# powercon_board.net
KiCad netlist of a schematic drawn in EAGLE
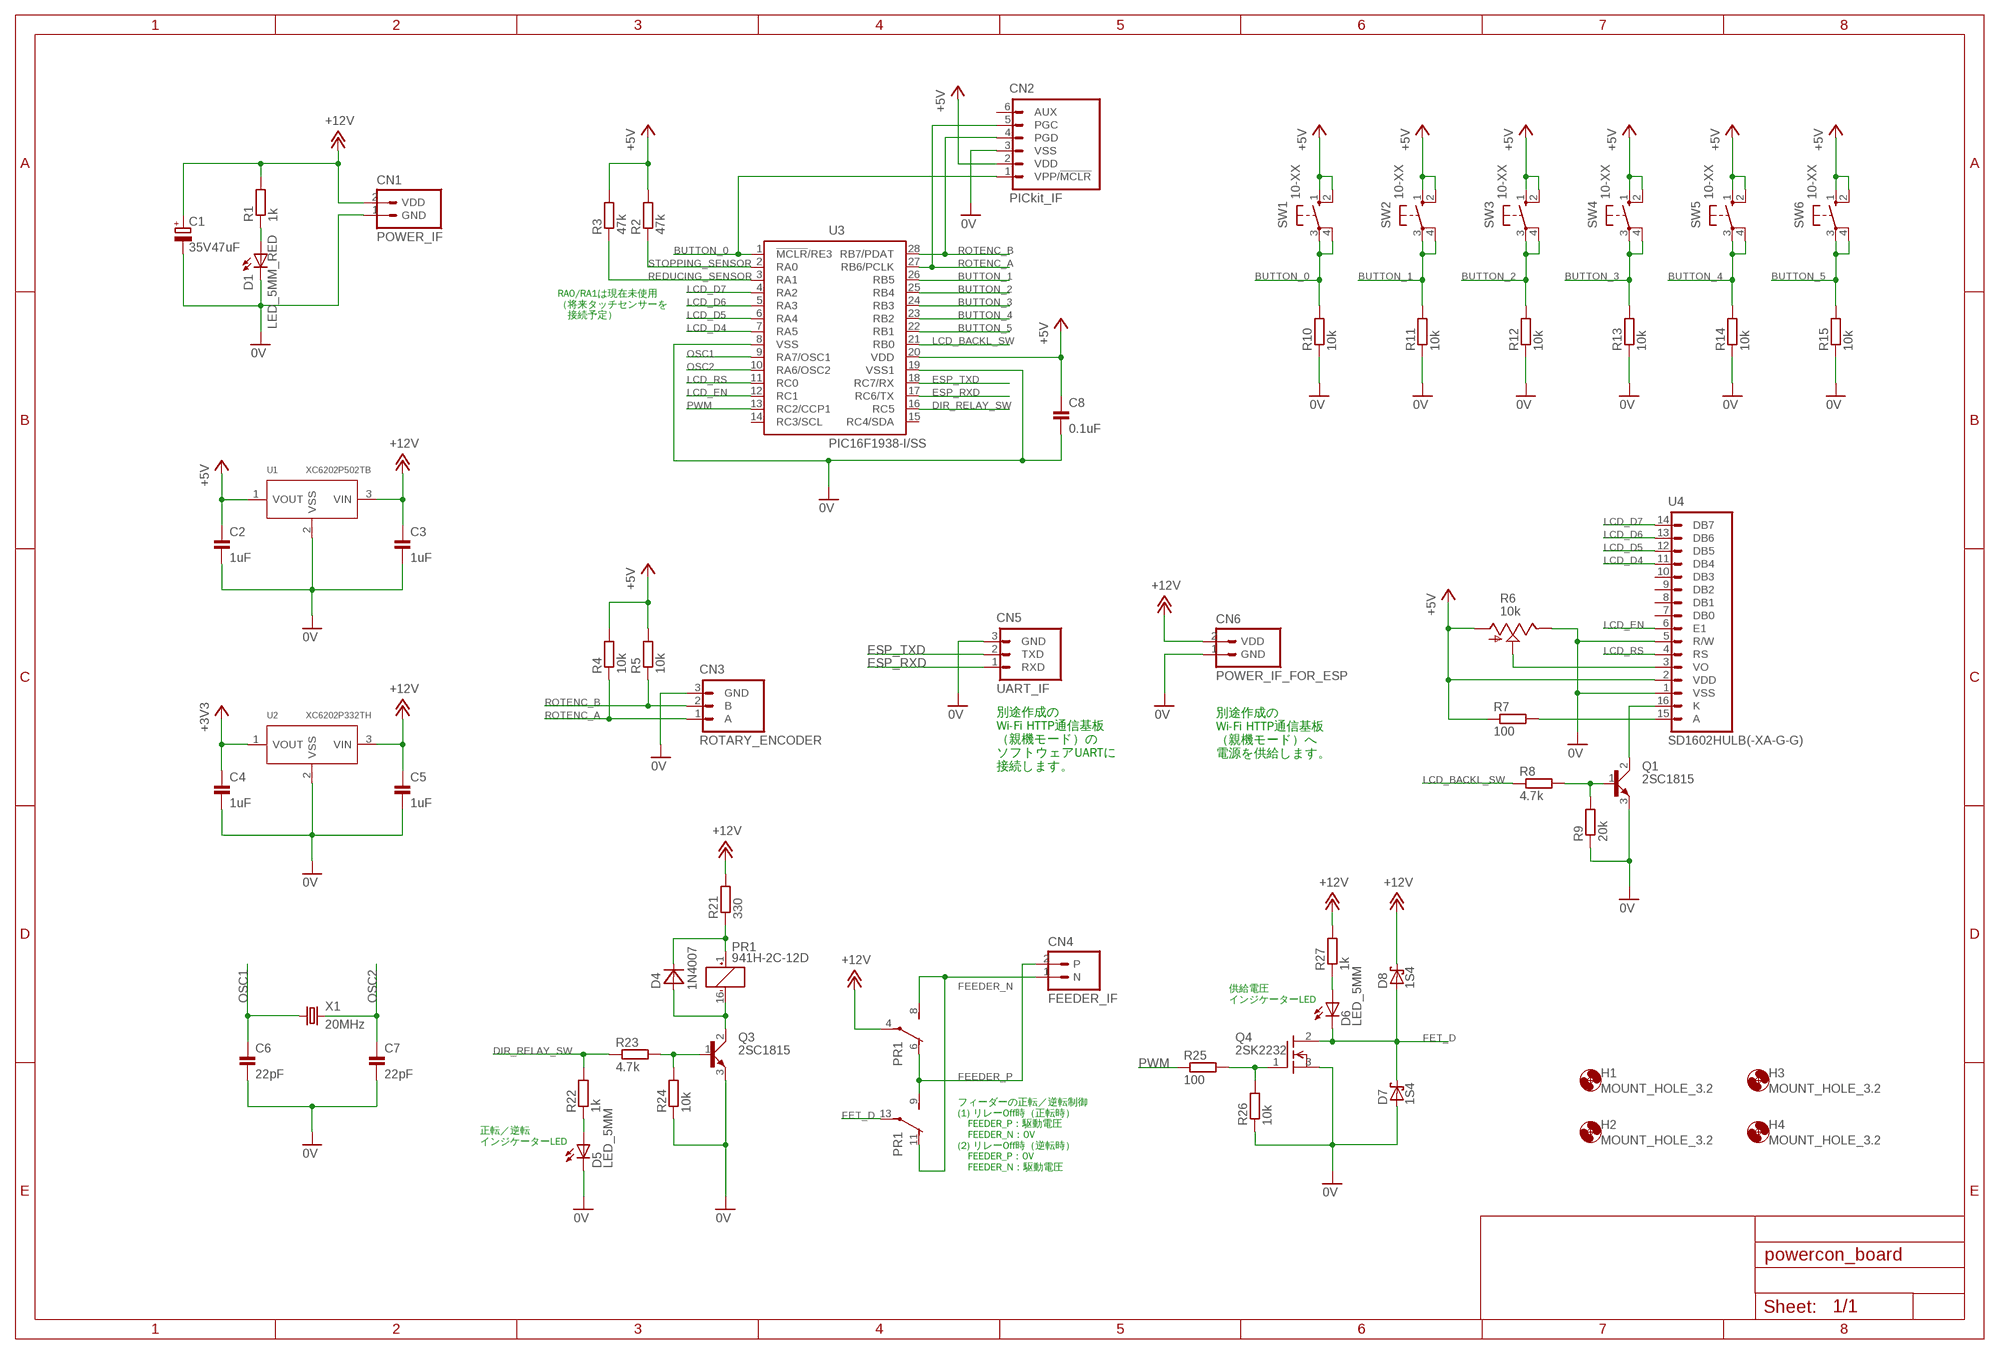
[diagram p0: schematic, sheet 1]

(export (version "E")
  (design (tool "Eeschema 10.0.6"))
  (components
    (comp (ref "C1")
      (value "35V47uF")
      (footprint "eagle-import:ELECAP_200MIL")
      (libsource (lib "eagle-import") (part "ELECAP_200MIL"))
    )
    (comp (ref "C2")
      (value "1uF")
      (footprint "eagle-import:CAP_200MIL")
      (libsource (lib "eagle-import") (part "CAP_200MIL"))
    )
    (comp (ref "C3")
      (value "1uF")
      (footprint "eagle-import:CAP_200MIL")
      (libsource (lib "eagle-import") (part "CAP_200MIL"))
    )
    (comp (ref "C4")
      (value "1uF")
      (footprint "eagle-import:CAP_200MIL")
      (libsource (lib "eagle-import") (part "CAP_200MIL"))
    )
    (comp (ref "C5")
      (value "1uF")
      (footprint "eagle-import:CAP_200MIL")
      (libsource (lib "eagle-import") (part "CAP_200MIL"))
    )
    (comp (ref "C6")
      (value "22pF")
      (footprint "eagle-import:CAP_200MIL")
      (libsource (lib "eagle-import") (part "CAP_200MIL"))
    )
    (comp (ref "C7")
      (value "22pF")
      (footprint "eagle-import:CAP_200MIL")
      (libsource (lib "eagle-import") (part "CAP_200MIL"))
    )
    (comp (ref "C8")
      (value "0.1uF")
      (footprint "eagle-import:CAP_200MIL")
      (libsource (lib "eagle-import") (part "CAP_200MIL"))
    )
    (comp (ref "CN1")
      (value "POWER_IF")
      (footprint "eagle-import:HEADER_2PIN_POWER_IF")
      (libsource (lib "eagle-import") (part "POWER_IF"))
    )
    (comp (ref "CN2")
      (value "PICkit_IF")
      (footprint "eagle-import:HEADER_6PIN")
      (libsource (lib "eagle-import") (part "PIC_CN_H"))
    )
    (comp (ref "CN3")
      (value "ROTARY_ENCODER")
      (footprint "eagle-import:HEADER_3PIN_ROT_ENC")
      (libsource (lib "eagle-import") (part "ROTARY_ENCODER"))
    )
    (comp (ref "CN4")
      (value "FEEDER_IF")
      (footprint "eagle-import:HEADER_2PIN_FEEDER_IF")
      (libsource (lib "eagle-import") (part "FEEDER_IF"))
    )
    (comp (ref "CN5")
      (value "UART_IF")
      (footprint "eagle-import:HEADER_3PIN_UART_IF")
      (libsource (lib "eagle-import") (part "UART_IF"))
    )
    (comp (ref "CN6")
      (value "POWER_IF_FOR_ESP")
      (footprint "eagle-import:HEADER_2PIN_POWER_IF")
      (libsource (lib "eagle-import") (part "POWER_IF"))
    )
    (comp (ref "D1")
      (value "LED_5MM_RED")
      (footprint "eagle-import:LED5MM")
      (libsource (lib "eagle-import") (part "LED_5MM"))
    )
    (comp (ref "D4")
      (value "1N4007")
      (footprint "eagle-import:DIODE_300MIL")
      (libsource (lib "eagle-import") (part "1N4007"))
    )
    (comp (ref "D5")
      (value "LED_5MM")
      (footprint "eagle-import:LED5MM")
      (libsource (lib "eagle-import") (part "LED_5MM"))
    )
    (comp (ref "D6")
      (value "LED_5MM")
      (footprint "eagle-import:LED5MM")
      (libsource (lib "eagle-import") (part "LED_5MM"))
    )
    (comp (ref "D7")
      (value "1S4")
      (footprint "eagle-import:DIODE-200MIL")
      (libsource (lib "eagle-import") (part "1S4"))
    )
    (comp (ref "D8")
      (value "1S4")
      (footprint "eagle-import:DIODE-200MIL")
      (libsource (lib "eagle-import") (part "1S4"))
    )
    (comp (ref "H1")
      (value "MOUNT_HOLE_3.2")
      (footprint "eagle-import:3,2")
      (libsource (lib "eagle-import") (part "MOUNT_HOLE_3.2"))
    )
    (comp (ref "H2")
      (value "MOUNT_HOLE_3.2")
      (footprint "eagle-import:3,2")
      (libsource (lib "eagle-import") (part "MOUNT_HOLE_3.2"))
    )
    (comp (ref "H3")
      (value "MOUNT_HOLE_3.2")
      (footprint "eagle-import:3,2")
      (libsource (lib "eagle-import") (part "MOUNT_HOLE_3.2"))
    )
    (comp (ref "H4")
      (value "MOUNT_HOLE_3.2")
      (footprint "eagle-import:3,2")
      (libsource (lib "eagle-import") (part "MOUNT_HOLE_3.2"))
    )
    (comp (ref "PR1")
      (value "941H-2C-12D")
      (footprint "eagle-import:941H-2C")
      (libsource (lib "eagle-import") (part "941H-2C-12D"))
    )
    (comp (ref "Q1")
      (value "2SC1815")
      (footprint "eagle-import:TO-92NL")
      (libsource (lib "eagle-import") (part "2SC1815"))
    )
    (comp (ref "Q3")
      (value "2SC1815")
      (footprint "eagle-import:TO-92NL")
      (libsource (lib "eagle-import") (part "2SC1815"))
    )
    (comp (ref "Q4")
      (value "2SK2232")
      (footprint "eagle-import:TO-220")
      (libsource (lib "eagle-import") (part "2SK2232"))
    )
    (comp (ref "R1")
      (value "1k")
      (footprint "eagle-import:RESISTOR_0207_300MIL")
      (libsource (lib "eagle-import") (part "RESISTOR_300MIL"))
    )
    (comp (ref "R2")
      (value "47k")
      (footprint "eagle-import:RESISTOR_0207_300MIL")
      (libsource (lib "eagle-import") (part "RESISTOR_300MIL"))
    )
    (comp (ref "R3")
      (value "47k")
      (footprint "eagle-import:RESISTOR_0207_300MIL")
      (libsource (lib "eagle-import") (part "RESISTOR_300MIL"))
    )
    (comp (ref "R4")
      (value "10k")
      (footprint "eagle-import:RESISTOR_0207_300MIL")
      (libsource (lib "eagle-import") (part "RESISTOR_300MIL"))
    )
    (comp (ref "R5")
      (value "10k")
      (footprint "eagle-import:RESISTOR_0207_300MIL")
      (libsource (lib "eagle-import") (part "RESISTOR_300MIL"))
    )
    (comp (ref "R6")
      (value "10k")
      (footprint "eagle-import:GF063XB")
      (libsource (lib "eagle-import") (part "GF063XB"))
    )
    (comp (ref "R7")
      (value "100")
      (footprint "eagle-import:RESISTOR_0207_300MIL")
      (libsource (lib "eagle-import") (part "RESISTOR_300MIL"))
    )
    (comp (ref "R8")
      (value "4.7k")
      (footprint "eagle-import:RESISTOR_0207_300MIL")
      (libsource (lib "eagle-import") (part "RESISTOR_300MIL"))
    )
    (comp (ref "R9")
      (value "20k")
      (footprint "eagle-import:RESISTOR_0207_300MIL")
      (libsource (lib "eagle-import") (part "RESISTOR_300MIL"))
    )
    (comp (ref "R10")
      (value "10k")
      (footprint "eagle-import:RESISTOR_0207_300MIL")
      (libsource (lib "eagle-import") (part "RESISTOR_300MIL"))
    )
    (comp (ref "R11")
      (value "10k")
      (footprint "eagle-import:RESISTOR_0207_300MIL")
      (libsource (lib "eagle-import") (part "RESISTOR_300MIL"))
    )
    (comp (ref "R12")
      (value "10k")
      (footprint "eagle-import:RESISTOR_0207_300MIL")
      (libsource (lib "eagle-import") (part "RESISTOR_300MIL"))
    )
    (comp (ref "R13")
      (value "10k")
      (footprint "eagle-import:RESISTOR_0207_300MIL")
      (libsource (lib "eagle-import") (part "RESISTOR_300MIL"))
    )
    (comp (ref "R14")
      (value "10k")
      (footprint "eagle-import:RESISTOR_0207_300MIL")
      (libsource (lib "eagle-import") (part "RESISTOR_300MIL"))
    )
    (comp (ref "R15")
      (value "10k")
      (footprint "eagle-import:RESISTOR_0207_300MIL")
      (libsource (lib "eagle-import") (part "RESISTOR_300MIL"))
    )
    (comp (ref "R21")
      (value "330")
      (footprint "eagle-import:RESISTOR_0207_300MIL")
      (libsource (lib "eagle-import") (part "RESISTOR_300MIL"))
    )
    (comp (ref "R22")
      (value "1k")
      (footprint "eagle-import:RESISTOR_0207_300MIL")
      (libsource (lib "eagle-import") (part "RESISTOR_300MIL"))
    )
    (comp (ref "R23")
      (value "4.7k")
      (footprint "eagle-import:RESISTOR_0207_300MIL")
      (libsource (lib "eagle-import") (part "RESISTOR_300MIL"))
    )
    (comp (ref "R24")
      (value "10k")
      (footprint "eagle-import:RESISTOR_0207_300MIL")
      (libsource (lib "eagle-import") (part "RESISTOR_300MIL"))
    )
    (comp (ref "R25")
      (value "100")
      (footprint "eagle-import:RESISTOR_0207_300MIL")
      (libsource (lib "eagle-import") (part "RESISTOR_300MIL"))
    )
    (comp (ref "R26")
      (value "10k")
      (footprint "eagle-import:RESISTOR_0207_300MIL")
      (libsource (lib "eagle-import") (part "RESISTOR_300MIL"))
    )
    (comp (ref "R27")
      (value "1k")
      (footprint "eagle-import:RESISTOR_0207_300MIL")
      (libsource (lib "eagle-import") (part "RESISTOR_300MIL"))
    )
    (comp (ref "SW1")
      (value "10-XX")
      (footprint "eagle-import:B3F-10XX")
      (libsource (lib "eagle-import") (part "10-XX"))
    )
    (comp (ref "SW2")
      (value "10-XX")
      (footprint "eagle-import:B3F-10XX")
      (libsource (lib "eagle-import") (part "10-XX"))
    )
    (comp (ref "SW3")
      (value "10-XX")
      (footprint "eagle-import:B3F-10XX")
      (libsource (lib "eagle-import") (part "10-XX"))
    )
    (comp (ref "SW4")
      (value "10-XX")
      (footprint "eagle-import:B3F-10XX")
      (libsource (lib "eagle-import") (part "10-XX"))
    )
    (comp (ref "SW5")
      (value "10-XX")
      (footprint "eagle-import:B3F-10XX")
      (libsource (lib "eagle-import") (part "10-XX"))
    )
    (comp (ref "SW6")
      (value "10-XX")
      (footprint "eagle-import:B3F-10XX")
      (libsource (lib "eagle-import") (part "10-XX"))
    )
    (comp (ref "U1")
      (value "XC6202P502TB")
      (footprint "eagle-import:TO92-LINE")
      (libsource (lib "eagle-import") (part "XC6202P502TB"))
    )
    (comp (ref "U2")
      (value "XC6202P332TH")
      (footprint "eagle-import:TO92-LINE")
      (libsource (lib "eagle-import") (part "XC6202P332TH"))
    )
    (comp (ref "U3")
      (value "PIC16F1938-I/SS")
      (footprint "eagle-import:SSOP28")
      (libsource (lib "eagle-import") (part "PIC16F1938-I/SS"))
    )
    (comp (ref "U4")
      (value "SD1602HULB(-XA-G-G)")
      (footprint "eagle-import:HEADER_16PIN_SD1602")
      (libsource (lib "eagle-import") (part "SD1602HULB(-XA-G-G)"))
    )
    (comp (ref "X1")
      (value "20MHz")
      (footprint "eagle-import:HC-49_S")
      (libsource (lib "eagle-import") (part "HUSG-20.000-20"))
    )
  )
  (nets
    (net (code "1") (name "+3V3") (class "Default")
      (node (ref "C4") (pin "1") (pinfunction "1_1") (pintype "passive"))
      (node (ref "U2") (pin "1") (pinfunction "VOUT_1") (pintype "passive"))
    )
    (net (code "2") (name "+5V") (class "Default")
      (node (ref "C2") (pin "1") (pinfunction "1_1") (pintype "passive"))
      (node (ref "C8") (pin "1") (pinfunction "1_1") (pintype "passive"))
      (node (ref "CN2") (pin "2") (pinfunction "VDD_2") (pintype "passive"))
      (node (ref "R2") (pin "2") (pinfunction "2_2") (pintype "passive"))
      (node (ref "R3") (pin "2") (pinfunction "2_2") (pintype "passive"))
      (node (ref "R4") (pin "2") (pinfunction "2_2") (pintype "passive"))
      (node (ref "R5") (pin "2") (pinfunction "2_2") (pintype "passive"))
      (node (ref "R6") (pin "A") (pinfunction "A_A") (pintype "passive"))
      (node (ref "R7") (pin "1") (pinfunction "1_1") (pintype "passive"))
      (node (ref "SW1") (pin "1") (pinfunction "S_1") (pintype "passive"))
      (node (ref "SW1") (pin "2") (pinfunction "S1_2") (pintype "passive"))
      (node (ref "SW2") (pin "1") (pinfunction "S_1") (pintype "passive"))
      (node (ref "SW2") (pin "2") (pinfunction "S1_2") (pintype "passive"))
      (node (ref "SW3") (pin "1") (pinfunction "S_1") (pintype "passive"))
      (node (ref "SW3") (pin "2") (pinfunction "S1_2") (pintype "passive"))
      (node (ref "SW4") (pin "1") (pinfunction "S_1") (pintype "passive"))
      (node (ref "SW4") (pin "2") (pinfunction "S1_2") (pintype "passive"))
      (node (ref "SW5") (pin "1") (pinfunction "S_1") (pintype "passive"))
      (node (ref "SW5") (pin "2") (pinfunction "S1_2") (pintype "passive"))
      (node (ref "SW6") (pin "1") (pinfunction "S_1") (pintype "passive"))
      (node (ref "SW6") (pin "2") (pinfunction "S1_2") (pintype "passive"))
      (node (ref "U1") (pin "1") (pinfunction "VOUT_1") (pintype "passive"))
      (node (ref "U3") (pin "20") (pinfunction "VDD_20") (pintype "passive"))
      (node (ref "U4") (pin "2") (pinfunction "VDD_2") (pintype "passive"))
    )
    (net (code "3") (name "+12V") (class "Default")
      (node (ref "C1") (pin "+") (pinfunction "+_+") (pintype "passive"))
      (node (ref "C3") (pin "1") (pinfunction "1_1") (pintype "passive"))
      (node (ref "C5") (pin "1") (pinfunction "1_1") (pintype "passive"))
      (node (ref "CN1") (pin "2") (pinfunction "VDD_2") (pintype "passive"))
      (node (ref "CN6") (pin "2") (pinfunction "VDD_2") (pintype "passive"))
      (node (ref "D8") (pin "C") (pinfunction "C_C") (pintype "passive"))
      (node (ref "PR1") (pin "4") (pinfunction "P_4") (pintype "passive"))
      (node (ref "R1") (pin "2") (pinfunction "2_2") (pintype "passive"))
      (node (ref "R21") (pin "2") (pinfunction "2_2") (pintype "passive"))
      (node (ref "R27") (pin "2") (pinfunction "2_2") (pintype "passive"))
      (node (ref "U1") (pin "3") (pinfunction "VIN_3") (pintype "passive"))
      (node (ref "U2") (pin "3") (pinfunction "VIN_3") (pintype "passive"))
    )
    (net (code "4") (name "/BUTTON_0") (class "Default")
      (node (ref "CN2") (pin "1") (pinfunction "VPP/~{MCLR}_1") (pintype "input"))
      (node (ref "R10") (pin "2") (pinfunction "2_2") (pintype "passive"))
      (node (ref "SW1") (pin "3") (pinfunction "P_3") (pintype "passive"))
      (node (ref "SW1") (pin "4") (pinfunction "P1_4") (pintype "passive"))
      (node (ref "U3") (pin "1") (pinfunction "~{MCLR}/RE3_1") (pintype "bidirectional"))
    )
    (net (code "5") (name "/BUTTON_1") (class "Default")
      (node (ref "R11") (pin "2") (pinfunction "2_2") (pintype "passive"))
      (node (ref "SW2") (pin "3") (pinfunction "P_3") (pintype "passive"))
      (node (ref "SW2") (pin "4") (pinfunction "P1_4") (pintype "passive"))
      (node (ref "U3") (pin "26") (pinfunction "RB5_26") (pintype "bidirectional"))
    )
    (net (code "6") (name "/BUTTON_2") (class "Default")
      (node (ref "R12") (pin "2") (pinfunction "2_2") (pintype "passive"))
      (node (ref "SW3") (pin "3") (pinfunction "P_3") (pintype "passive"))
      (node (ref "SW3") (pin "4") (pinfunction "P1_4") (pintype "passive"))
      (node (ref "U3") (pin "25") (pinfunction "RB4_25") (pintype "bidirectional"))
    )
    (net (code "7") (name "/BUTTON_3") (class "Default")
      (node (ref "R13") (pin "2") (pinfunction "2_2") (pintype "passive"))
      (node (ref "SW4") (pin "3") (pinfunction "P_3") (pintype "passive"))
      (node (ref "SW4") (pin "4") (pinfunction "P1_4") (pintype "passive"))
      (node (ref "U3") (pin "24") (pinfunction "RB3_24") (pintype "bidirectional"))
    )
    (net (code "8") (name "/BUTTON_4") (class "Default")
      (node (ref "R14") (pin "2") (pinfunction "2_2") (pintype "passive"))
      (node (ref "SW5") (pin "3") (pinfunction "P_3") (pintype "passive"))
      (node (ref "SW5") (pin "4") (pinfunction "P1_4") (pintype "passive"))
      (node (ref "U3") (pin "23") (pinfunction "RB2_23") (pintype "bidirectional"))
    )
    (net (code "9") (name "/BUTTON_5") (class "Default")
      (node (ref "R15") (pin "2") (pinfunction "2_2") (pintype "passive"))
      (node (ref "SW6") (pin "3") (pinfunction "P_3") (pintype "passive"))
      (node (ref "SW6") (pin "4") (pinfunction "P1_4") (pintype "passive"))
      (node (ref "U3") (pin "22") (pinfunction "RB1_22") (pintype "bidirectional"))
    )
    (net (code "10") (name "/DIR_RELAY_SW") (class "Default")
      (node (ref "R22") (pin "2") (pinfunction "2_2") (pintype "passive"))
      (node (ref "R23") (pin "1") (pinfunction "1_1") (pintype "passive"))
      (node (ref "U3") (pin "16") (pinfunction "RC5_16") (pintype "bidirectional"))
    )
    (net (code "11") (name "/ESP_RXD") (class "Default")
      (node (ref "CN5") (pin "1") (pinfunction "RXD_1") (pintype "bidirectional"))
      (node (ref "U3") (pin "17") (pinfunction "RC6/TX_17") (pintype "bidirectional"))
    )
    (net (code "12") (name "/ESP_TXD") (class "Default")
      (node (ref "CN5") (pin "2") (pinfunction "TXD_2") (pintype "bidirectional"))
      (node (ref "U3") (pin "18") (pinfunction "RC7/RX_18") (pintype "bidirectional"))
    )
    (net (code "13") (name "/FEEDER_N") (class "Default")
      (node (ref "CN4") (pin "1") (pinfunction "N_1") (pintype "passive"))
      (node (ref "PR1") (pin "11") (pinfunction "O_11") (pintype "passive"))
      (node (ref "PR1") (pin "8") (pinfunction "S_8") (pintype "passive"))
    )
    (net (code "14") (name "/FEEDER_P") (class "Default")
      (node (ref "CN4") (pin "2") (pinfunction "P_2") (pintype "passive"))
      (node (ref "PR1") (pin "6") (pinfunction "O_6") (pintype "passive"))
      (node (ref "PR1") (pin "9") (pinfunction "S_9") (pintype "passive"))
    )
    (net (code "15") (name "/FET_D") (class "Default")
      (node (ref "D6") (pin "K") (pinfunction "C_K") (pintype "passive"))
      (node (ref "D7") (pin "C") (pinfunction "C_C") (pintype "passive"))
      (node (ref "D8") (pin "A") (pinfunction "A_A") (pintype "passive"))
      (node (ref "PR1") (pin "13") (pinfunction "P_13") (pintype "passive"))
      (node (ref "Q4") (pin "2") (pinfunction "D_2") (pintype "passive"))
    )
    (net (code "16") (name "/LCD_BACKL_SW") (class "Default")
      (node (ref "R8") (pin "1") (pinfunction "1_1") (pintype "passive"))
      (node (ref "U3") (pin "21") (pinfunction "RB0_21") (pintype "bidirectional"))
    )
    (net (code "17") (name "/LCD_D4") (class "Default")
      (node (ref "U3") (pin "7") (pinfunction "RA5_7") (pintype "bidirectional"))
      (node (ref "U4") (pin "11") (pinfunction "DB4_11") (pintype "bidirectional"))
    )
    (net (code "18") (name "/LCD_D5") (class "Default")
      (node (ref "U3") (pin "6") (pinfunction "RA4_6") (pintype "bidirectional"))
      (node (ref "U4") (pin "12") (pinfunction "DB5_12") (pintype "bidirectional"))
    )
    (net (code "19") (name "/LCD_D6") (class "Default")
      (node (ref "U3") (pin "5") (pinfunction "RA3_5") (pintype "bidirectional"))
      (node (ref "U4") (pin "13") (pinfunction "DB6_13") (pintype "bidirectional"))
    )
    (net (code "20") (name "/LCD_D7") (class "Default")
      (node (ref "U3") (pin "4") (pinfunction "RA2_4") (pintype "bidirectional"))
      (node (ref "U4") (pin "14") (pinfunction "DB7_14") (pintype "bidirectional"))
    )
    (net (code "21") (name "/LCD_EN") (class "Default")
      (node (ref "U3") (pin "12") (pinfunction "RC1_12") (pintype "bidirectional"))
      (node (ref "U4") (pin "6") (pinfunction "E1_6") (pintype "bidirectional"))
    )
    (net (code "22") (name "/LCD_RS") (class "Default")
      (node (ref "U3") (pin "11") (pinfunction "RC0_11") (pintype "bidirectional"))
      (node (ref "U4") (pin "4") (pinfunction "RS_4") (pintype "bidirectional"))
    )
    (net (code "23") (name "/OSC1") (class "Default")
      (node (ref "C6") (pin "1") (pinfunction "1_1") (pintype "passive"))
      (node (ref "U3") (pin "9") (pinfunction "RA7/OSC1_9") (pintype "bidirectional"))
      (node (ref "X1") (pin "1") (pinfunction "1_1") (pintype "passive"))
    )
    (net (code "24") (name "/OSC2") (class "Default")
      (node (ref "C7") (pin "1") (pinfunction "1_1") (pintype "passive"))
      (node (ref "U3") (pin "10") (pinfunction "RA6/OSC2_10") (pintype "bidirectional"))
      (node (ref "X1") (pin "2") (pinfunction "2_2") (pintype "passive"))
    )
    (net (code "25") (name "/PWM") (class "Default")
      (node (ref "R25") (pin "1") (pinfunction "1_1") (pintype "passive"))
      (node (ref "U3") (pin "13") (pinfunction "RC2/CCP1_13") (pintype "bidirectional"))
    )
    (net (code "26") (name "/REDUCING_SENSOR") (class "Default")
      (node (ref "R3") (pin "1") (pinfunction "1_1") (pintype "passive"))
      (node (ref "U3") (pin "3") (pinfunction "RA1_3") (pintype "bidirectional"))
    )
    (net (code "27") (name "/ROTENC_A") (class "Default")
      (node (ref "CN2") (pin "5") (pinfunction "PGC_5") (pintype "input"))
      (node (ref "CN3") (pin "1") (pinfunction "A_1") (pintype "bidirectional"))
      (node (ref "R4") (pin "1") (pinfunction "1_1") (pintype "passive"))
      (node (ref "U3") (pin "27") (pinfunction "RB6/PCLK_27") (pintype "bidirectional"))
    )
    (net (code "28") (name "/ROTENC_B") (class "Default")
      (node (ref "CN2") (pin "4") (pinfunction "PGD_4") (pintype "bidirectional"))
      (node (ref "CN3") (pin "2") (pinfunction "B_2") (pintype "bidirectional"))
      (node (ref "R5") (pin "1") (pinfunction "1_1") (pintype "passive"))
      (node (ref "U3") (pin "28") (pinfunction "RB7/PDAT_28") (pintype "bidirectional"))
    )
    (net (code "29") (name "/STOPPING_SENSOR") (class "Default")
      (node (ref "R2") (pin "1") (pinfunction "1_1") (pintype "passive"))
      (node (ref "U3") (pin "2") (pinfunction "RA0_2") (pintype "bidirectional"))
    )
    (net (code "30") (name "0V") (class "Default")
      (node (ref "C1") (pin "-") (pinfunction "-_-") (pintype "passive"))
      (node (ref "C2") (pin "2") (pinfunction "2_2") (pintype "passive"))
      (node (ref "C3") (pin "2") (pinfunction "2_2") (pintype "passive"))
      (node (ref "C4") (pin "2") (pinfunction "2_2") (pintype "passive"))
      (node (ref "C5") (pin "2") (pinfunction "2_2") (pintype "passive"))
      (node (ref "C6") (pin "2") (pinfunction "2_2") (pintype "passive"))
      (node (ref "C7") (pin "2") (pinfunction "2_2") (pintype "passive"))
      (node (ref "C8") (pin "2") (pinfunction "2_2") (pintype "passive"))
      (node (ref "CN1") (pin "1") (pinfunction "GND_1") (pintype "passive"))
      (node (ref "CN2") (pin "3") (pinfunction "VSS_3") (pintype "passive"))
      (node (ref "CN3") (pin "3") (pinfunction "GND_3") (pintype "passive"))
      (node (ref "CN5") (pin "3") (pinfunction "GND_3") (pintype "passive"))
      (node (ref "CN6") (pin "1") (pinfunction "GND_1") (pintype "passive"))
      (node (ref "D1") (pin "K") (pinfunction "C_K") (pintype "passive"))
      (node (ref "D5") (pin "K") (pinfunction "C_K") (pintype "passive"))
      (node (ref "D7") (pin "A") (pinfunction "A_A") (pintype "passive"))
      (node (ref "Q1") (pin "3") (pinfunction "E_3") (pintype "passive"))
      (node (ref "Q3") (pin "3") (pinfunction "E_3") (pintype "passive"))
      (node (ref "Q4") (pin "3") (pinfunction "S_3") (pintype "passive"))
      (node (ref "R10") (pin "1") (pinfunction "1_1") (pintype "passive"))
      (node (ref "R11") (pin "1") (pinfunction "1_1") (pintype "passive"))
      (node (ref "R12") (pin "1") (pinfunction "1_1") (pintype "passive"))
      (node (ref "R13") (pin "1") (pinfunction "1_1") (pintype "passive"))
      (node (ref "R14") (pin "1") (pinfunction "1_1") (pintype "passive"))
      (node (ref "R15") (pin "1") (pinfunction "1_1") (pintype "passive"))
      (node (ref "R24") (pin "1") (pinfunction "1_1") (pintype "passive"))
      (node (ref "R26") (pin "1") (pinfunction "1_1") (pintype "passive"))
      (node (ref "R6") (pin "E") (pinfunction "E_E") (pintype "passive"))
      (node (ref "R9") (pin "1") (pinfunction "1_1") (pintype "passive"))
      (node (ref "U1") (pin "2") (pinfunction "VSS_2") (pintype "passive"))
      (node (ref "U2") (pin "2") (pinfunction "VSS_2") (pintype "passive"))
      (node (ref "U3") (pin "19") (pinfunction "VSS1_19") (pintype "passive"))
      (node (ref "U3") (pin "8") (pinfunction "VSS_8") (pintype "passive"))
      (node (ref "U4") (pin "1") (pinfunction "VSS_1") (pintype "passive"))
      (node (ref "U4") (pin "5") (pinfunction "R/W_5") (pintype "bidirectional"))
    )
    (net (code "31") (name "Net-(D1-PadA)") (class "Default")
      (node (ref "D1") (pin "A") (pinfunction "A_A") (pintype "passive"))
      (node (ref "R1") (pin "1") (pinfunction "1_1") (pintype "passive"))
    )
    (net (code "32") (name "Net-(D5-PadA)") (class "Default")
      (node (ref "D5") (pin "A") (pinfunction "A_A") (pintype "passive"))
      (node (ref "R22") (pin "1") (pinfunction "1_1") (pintype "passive"))
    )
    (net (code "33") (name "Net-(D6-PadA)") (class "Default")
      (node (ref "D6") (pin "A") (pinfunction "A_A") (pintype "passive"))
      (node (ref "R27") (pin "1") (pinfunction "1_1") (pintype "passive"))
    )
    (net (code "34") (name "Net-(PR1A-+)") (class "Default")
      (node (ref "D4") (pin "C") (pinfunction "C_C") (pintype "passive"))
      (node (ref "PR1") (pin "1") (pinfunction "+_1") (pintype "passive"))
      (node (ref "R21") (pin "1") (pinfunction "1_1") (pintype "passive"))
    )
    (net (code "35") (name "Net-(PR1A--)") (class "Default")
      (node (ref "D4") (pin "A") (pinfunction "A_A") (pintype "passive"))
      (node (ref "PR1") (pin "16") (pinfunction "-_16") (pintype "passive"))
      (node (ref "Q3") (pin "2") (pinfunction "C_2") (pintype "passive"))
    )
    (net (code "36") (name "Net-(Q1-B)") (class "Default")
      (node (ref "Q1") (pin "1") (pinfunction "B_1") (pintype "passive"))
      (node (ref "R8") (pin "2") (pinfunction "2_2") (pintype "passive"))
      (node (ref "R9") (pin "2") (pinfunction "2_2") (pintype "passive"))
    )
    (net (code "37") (name "Net-(Q1-C)") (class "Default")
      (node (ref "Q1") (pin "2") (pinfunction "C_2") (pintype "passive"))
      (node (ref "U4") (pin "16") (pinfunction "K_16") (pintype "passive"))
    )
    (net (code "38") (name "Net-(Q3-B)") (class "Default")
      (node (ref "Q3") (pin "1") (pinfunction "B_1") (pintype "passive"))
      (node (ref "R23") (pin "2") (pinfunction "2_2") (pintype "passive"))
      (node (ref "R24") (pin "2") (pinfunction "2_2") (pintype "passive"))
    )
    (net (code "39") (name "Net-(Q4-G)") (class "Default")
      (node (ref "Q4") (pin "1") (pinfunction "G_1") (pintype "passive"))
      (node (ref "R25") (pin "2") (pinfunction "2_2") (pintype "passive"))
      (node (ref "R26") (pin "2") (pinfunction "2_2") (pintype "passive"))
    )
    (net (code "40") (name "Net-(U4-A)") (class "Default")
      (node (ref "R7") (pin "2") (pinfunction "2_2") (pintype "passive"))
      (node (ref "U4") (pin "15") (pinfunction "A_15") (pintype "passive"))
    )
    (net (code "41") (name "Net-(U4-VO)") (class "Default")
      (node (ref "R6") (pin "S") (pinfunction "S_S") (pintype "passive"))
      (node (ref "U4") (pin "3") (pinfunction "VO_3") (pintype "passive"))
    )
    (net (code "42") (name "unconnected-(CN2-AUX-Pad6)") (class "Default")
      (node (ref "CN2") (pin "6") (pinfunction "AUX_6") (pintype "bidirectional"))
    )
    (net (code "43") (name "unconnected-(U3-RC3{slash}SCL-Pad14)") (class "Default")
      (node (ref "U3") (pin "14") (pinfunction "RC3/SCL_14") (pintype "bidirectional"))
    )
    (net (code "44") (name "unconnected-(U3-RC4{slash}SDA-Pad15)") (class "Default")
      (node (ref "U3") (pin "15") (pinfunction "RC4/SDA_15") (pintype "bidirectional"))
    )
    (net (code "45") (name "unconnected-(U4-DB0-Pad7)") (class "Default")
      (node (ref "U4") (pin "7") (pinfunction "DB0_7") (pintype "bidirectional"))
    )
    (net (code "46") (name "unconnected-(U4-DB1-Pad8)") (class "Default")
      (node (ref "U4") (pin "8") (pinfunction "DB1_8") (pintype "bidirectional"))
    )
    (net (code "47") (name "unconnected-(U4-DB2-Pad9)") (class "Default")
      (node (ref "U4") (pin "9") (pinfunction "DB2_9") (pintype "bidirectional"))
    )
    (net (code "48") (name "unconnected-(U4-DB3-Pad10)") (class "Default")
      (node (ref "U4") (pin "10") (pinfunction "DB3_10") (pintype "bidirectional"))
    )
  )
)
